# controller_rev4_2.net
KiCad netlist of a schematic drawn in EAGLE
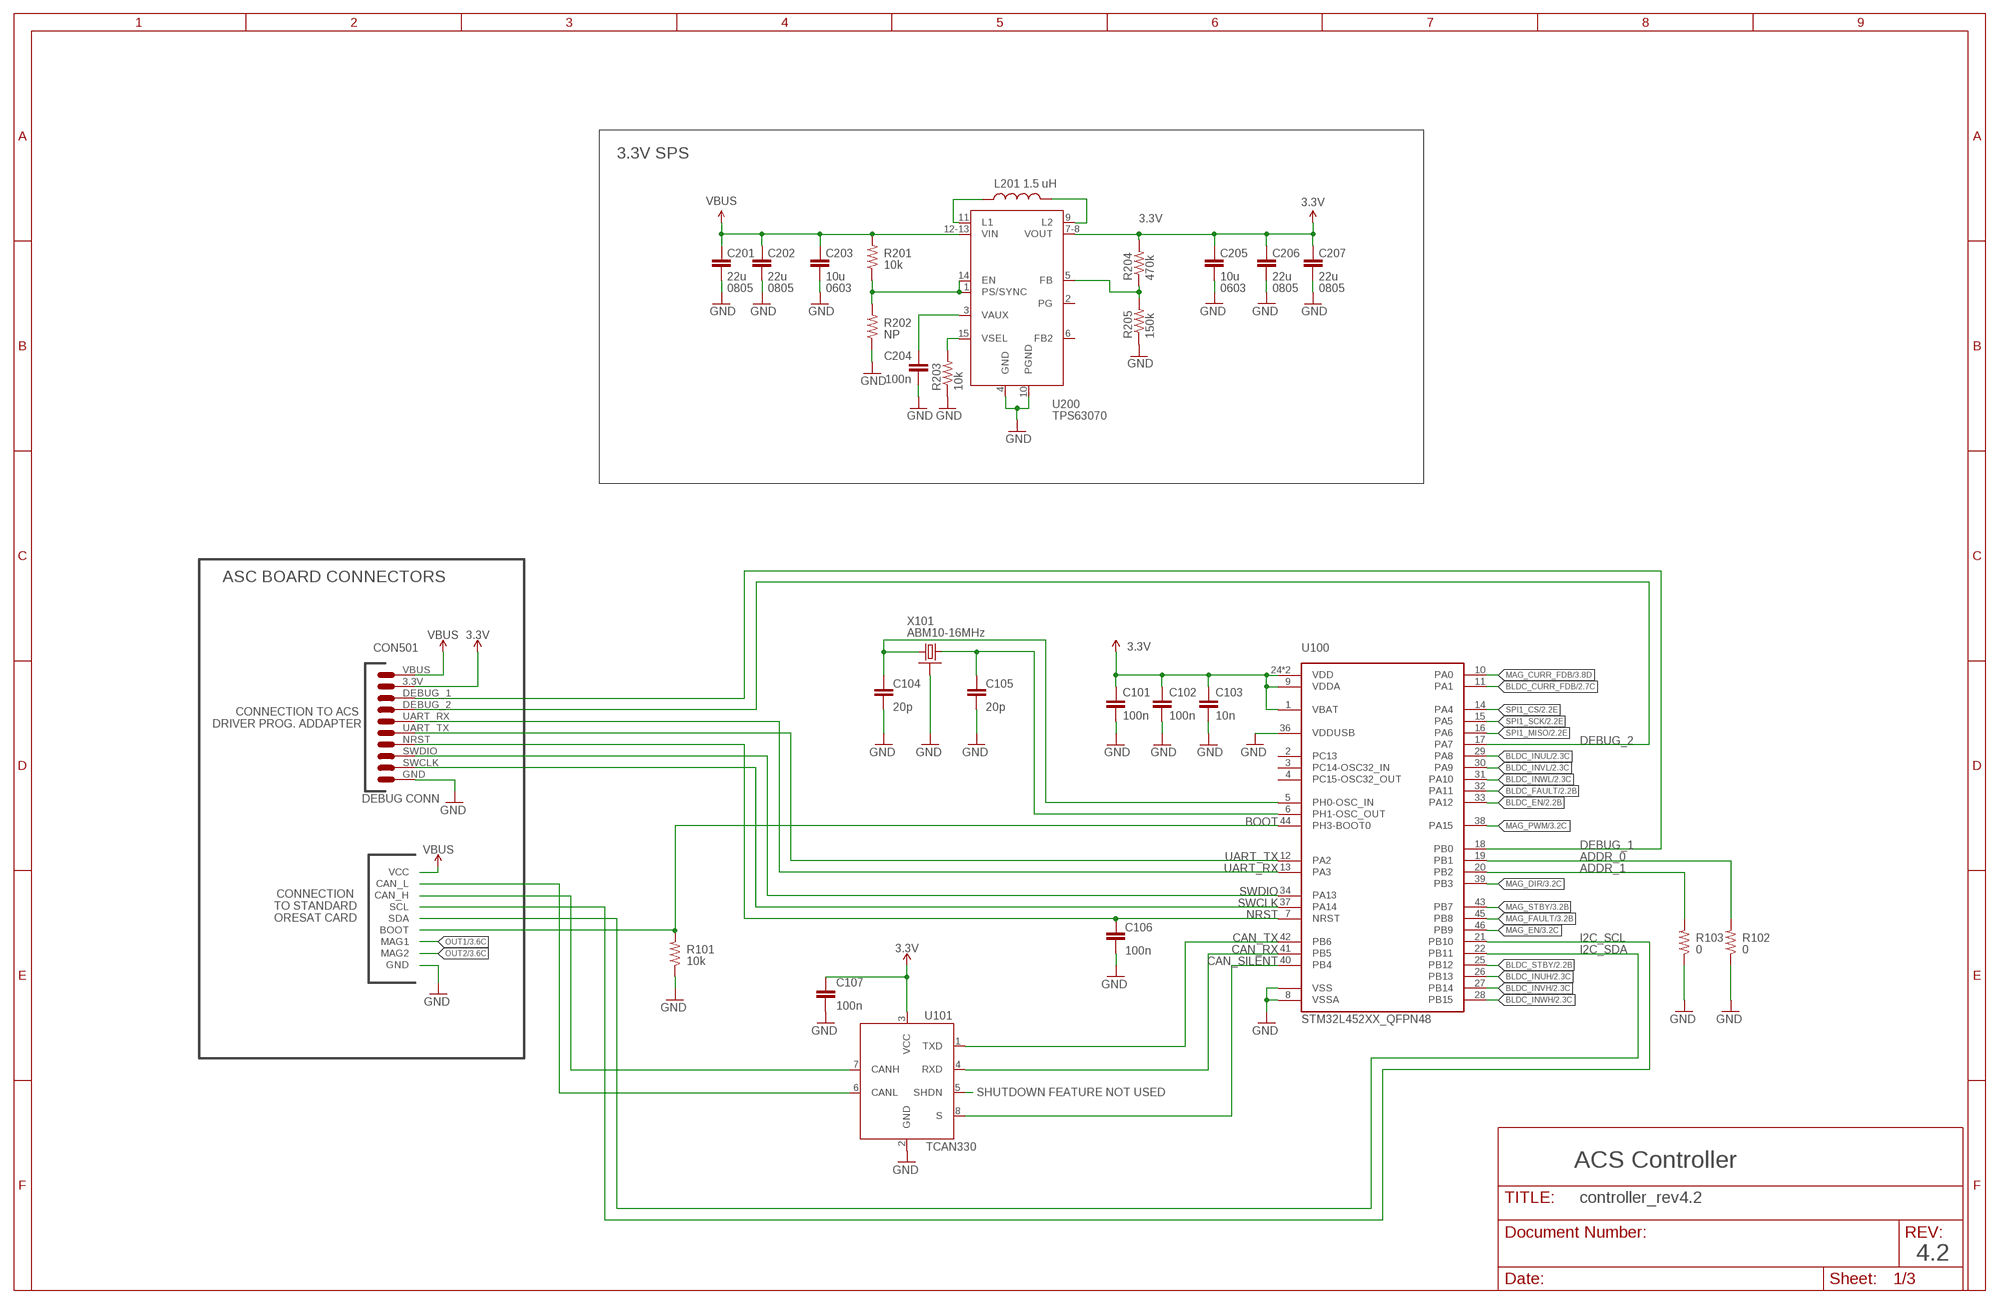
[diagram p0: schematic, sheet 1]
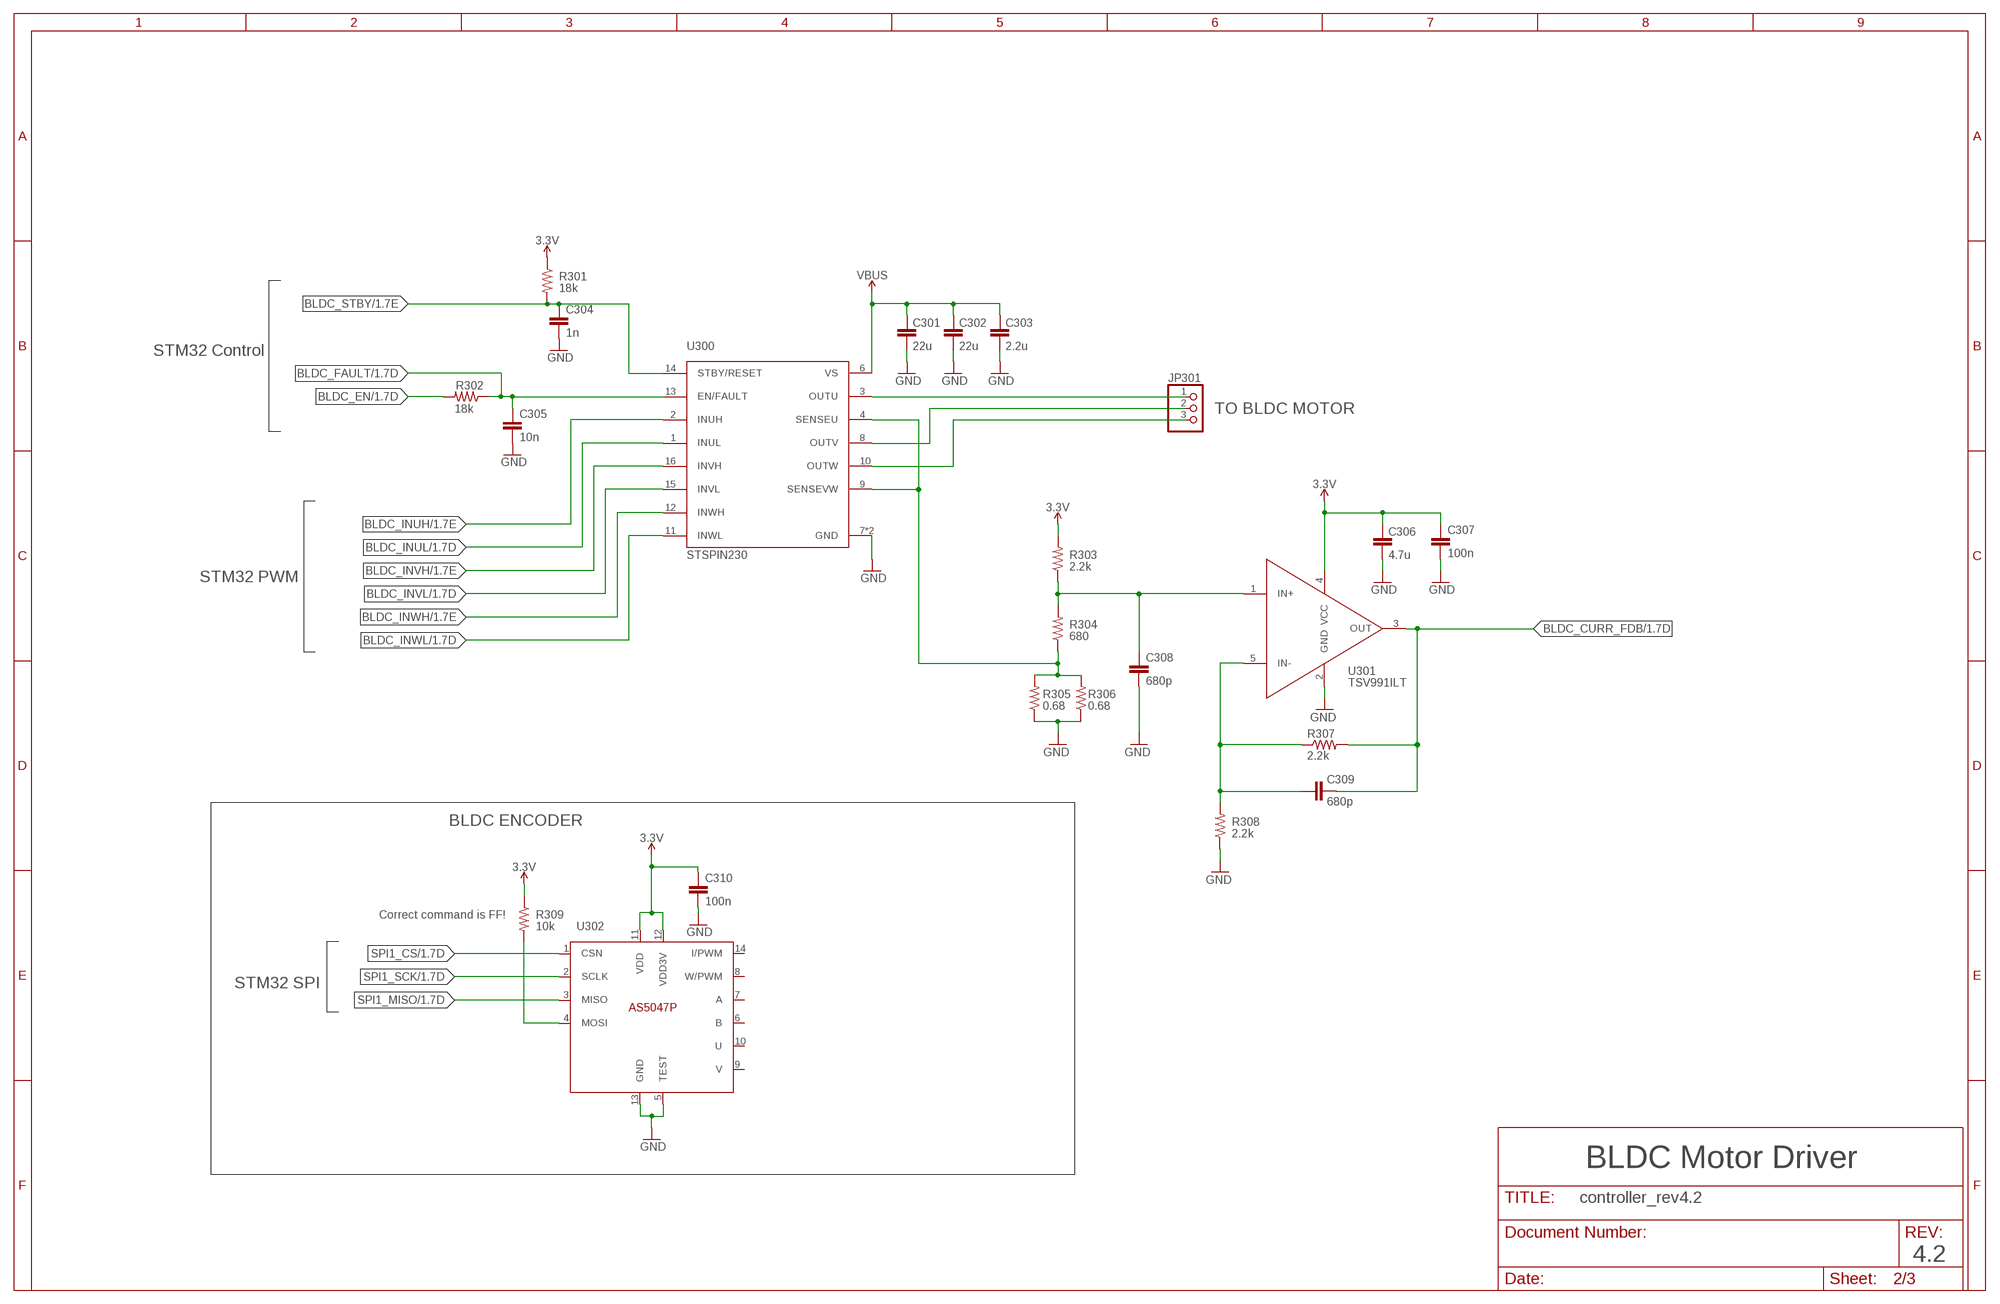
[diagram p1: schematic, sheet 2]
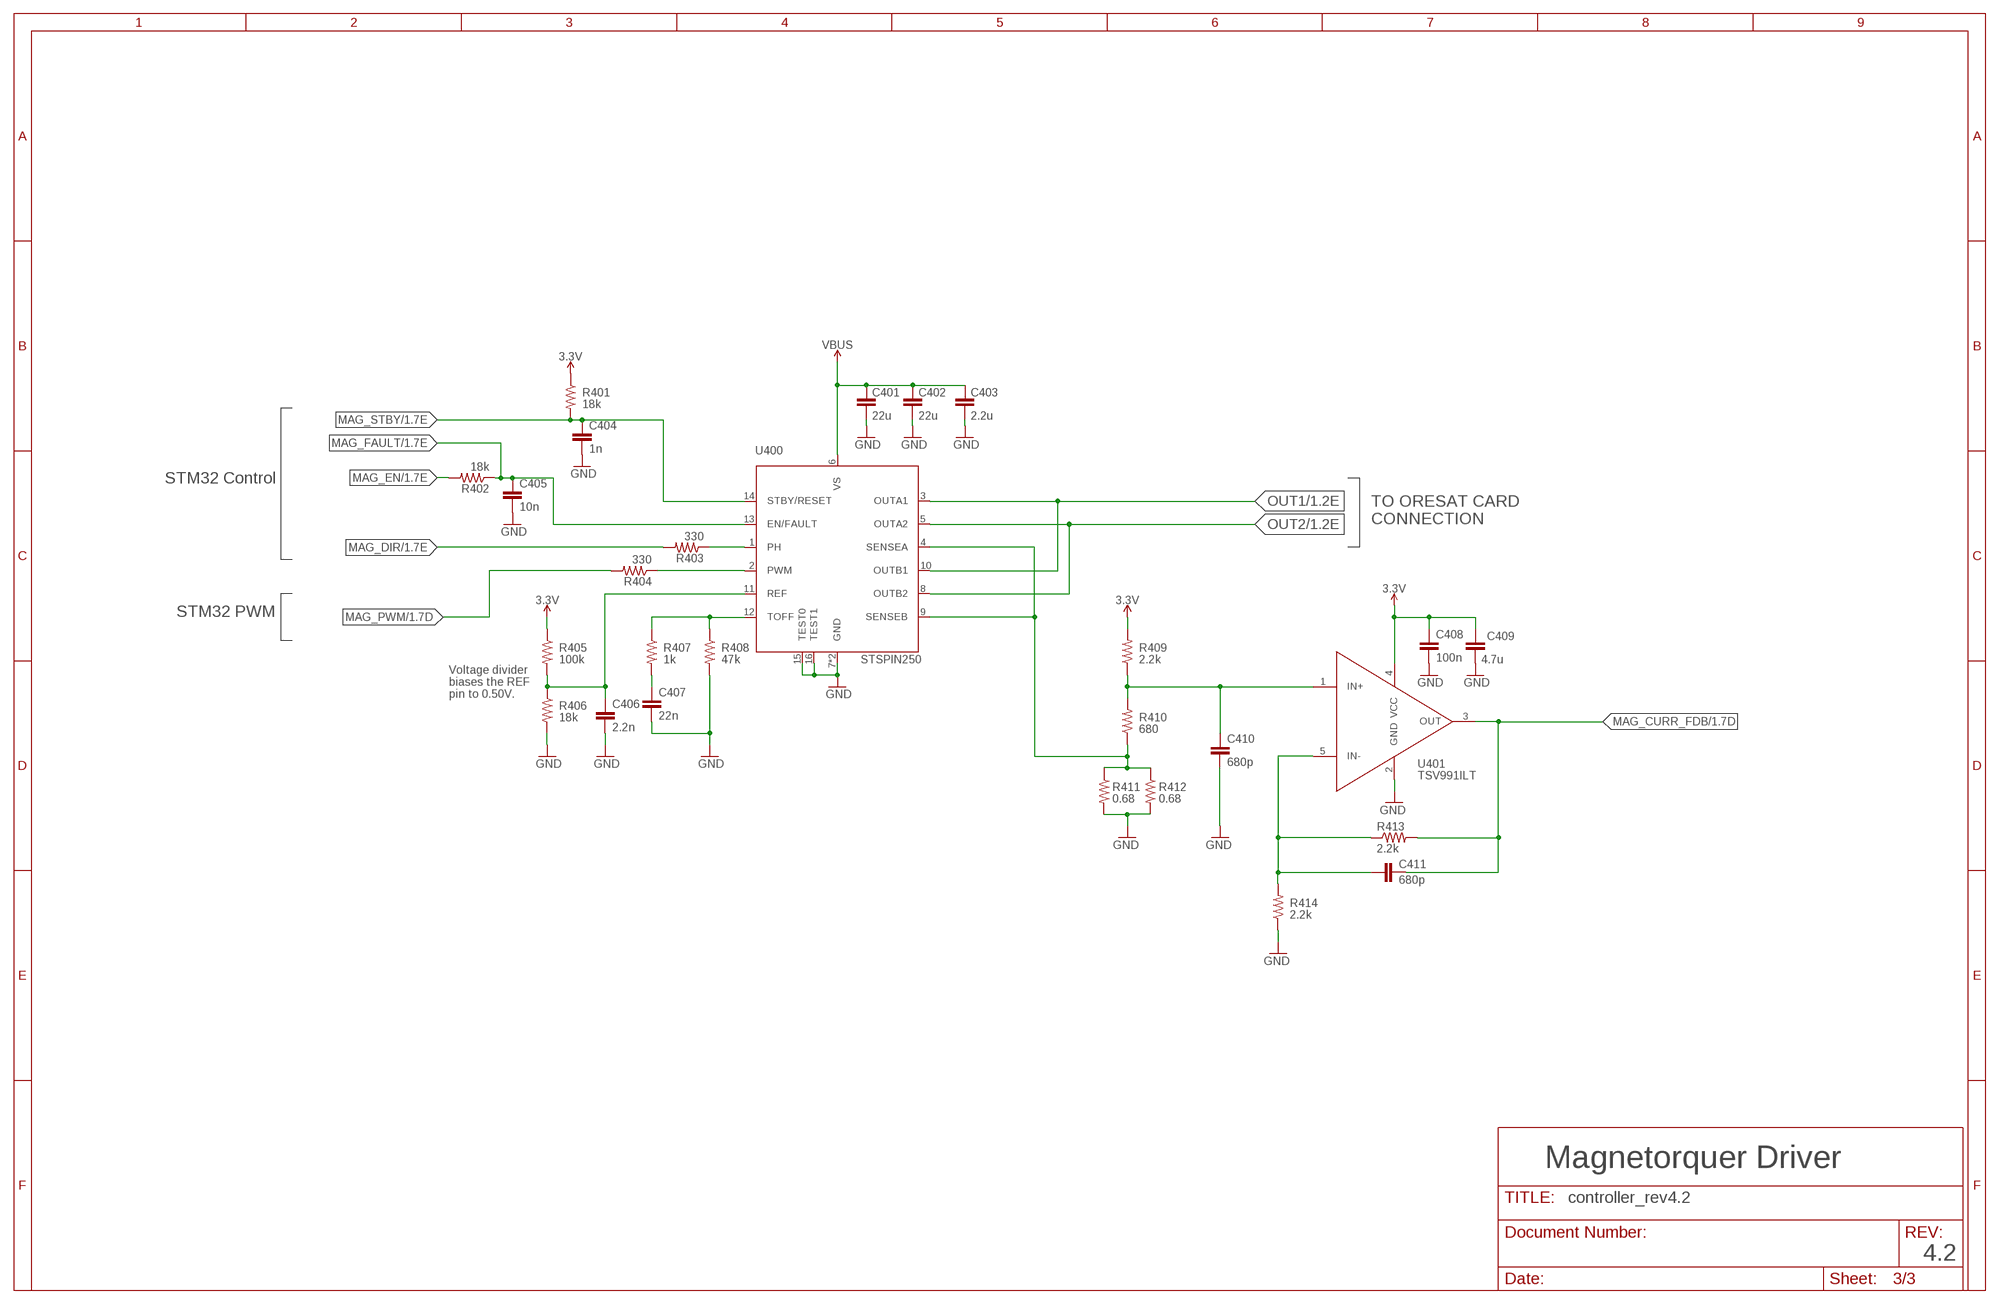
[diagram p2: schematic, sheet 3]

(export (version "E")
  (design (tool "Eeschema 10.0.6"))
  (components
    (comp (ref "C401")
      (value "22u")
      (footprint "eagle-import:.0603-B-NOSILK")
      (fields (field (name "MFR") "Samsung") (field (name "MPN") "CL05B104KO5NNNC"))
      (libsource (lib "eagle-import") (part "C-EU0603-B-NOSILK"))
    )
    (comp (ref "C402")
      (value "22u")
      (footprint "eagle-import:.0603-B-NOSILK")
      (fields (field (name "MFR") "Samsung") (field (name "MPN") "CL05B104KO5NNNC"))
      (libsource (lib "eagle-import") (part "C-EU0603-B-NOSILK"))
    )
    (comp (ref "C403")
      (value "2.2u")
      (footprint "eagle-import:.0603-B-NOSILK")
      (fields (field (name "MFR") "Samsung") (field (name "MPN") "CL05B104KO5NNNC"))
      (libsource (lib "eagle-import") (part "C-EU0603-B-NOSILK"))
    )
    (comp (ref "C404")
      (value "1n")
      (footprint "eagle-import:.0402-B-NOSILK")
      (fields (field (name "MFR") "Samsung") (field (name "MPN") "CL05B104KO5NNNC"))
      (libsource (lib "eagle-import") (part "rcl_custom_C-EU0402-B-NOSILK"))
    )
    (comp (ref "C405")
      (value "10n")
      (footprint "eagle-import:.0402-B-NOSILK")
      (fields (field (name "MFR") "Samsung") (field (name "MPN") "CL05B104KO5NNNC"))
      (libsource (lib "eagle-import") (part "rcl_custom_C-EU0402-B-NOSILK"))
    )
    (comp (ref "C406")
      (value "2.2n")
      (footprint "eagle-import:.0402-B-NOSILK")
      (fields (field (name "MFR") "Samsung") (field (name "MPN") "CL05B104KO5NNNC"))
      (libsource (lib "eagle-import") (part "rcl_custom_C-EU0402-B-NOSILK"))
    )
    (comp (ref "C407")
      (value "22n")
      (footprint "eagle-import:.0402-B-NOSILK")
      (fields (field (name "MFR") "Samsung") (field (name "MPN") "CL05B104KO5NNNC"))
      (libsource (lib "eagle-import") (part "rcl_custom_C-EU0402-B-NOSILK"))
    )
    (comp (ref "C408")
      (value "100n")
      (footprint "eagle-import:.0402-B-NOSILK")
      (fields (field (name "MFR") "Samsung") (field (name "MPN") "CL05B104KO5NNNC"))
      (libsource (lib "eagle-import") (part "rcl_custom_C-EU0402-B-NOSILK"))
    )
    (comp (ref "C409")
      (value "4.7u")
      (footprint "eagle-import:.0603-B-NOSILK")
      (fields (field (name "MFR") "Samsung") (field (name "MPN") "CL05B104KO5NNNC"))
      (libsource (lib "eagle-import") (part "C-EU0603-B-NOSILK"))
    )
    (comp (ref "C410")
      (value "680p")
      (footprint "eagle-import:.0402-B-NOSILK")
      (fields (field (name "MFR") "Samsung") (field (name "MPN") "CL05B104KO5NNNC"))
      (libsource (lib "eagle-import") (part "rcl_custom_C-EU0402-B-NOSILK"))
    )
    (comp (ref "C411")
      (value "680p")
      (footprint "eagle-import:.0402-B-NOSILK")
      (fields (field (name "MFR") "Samsung") (field (name "MPN") "CL05B104KO5NNNC"))
      (libsource (lib "eagle-import") (part "rcl_custom_C-EU0402-B-NOSILK"))
    )
    (comp (ref "R401")
      (value "18k")
      (footprint "eagle-import:.0402-B-NOSILK")
      (fields (field (name "MFR") "Samsung") (field (name "MPN") "RC1005F6653CS"))
      (libsource (lib "eagle-import") (part "rcl_custom_R-US_0402-B-NOSILK"))
    )
    (comp (ref "R402")
      (value "18k")
      (footprint "eagle-import:.0402-B-NOSILK")
      (fields (field (name "MFR") "Samsung") (field (name "MPN") "RC1005F6653CS"))
      (libsource (lib "eagle-import") (part "rcl_custom_R-US_0402-B-NOSILK"))
    )
    (comp (ref "R403")
      (value "330")
      (footprint "eagle-import:.0402-B-NOSILK")
      (fields (field (name "MFR") "Samsung") (field (name "MPN") "RC1005F6653CS"))
      (libsource (lib "eagle-import") (part "rcl_custom_R-US_0402-B-NOSILK"))
    )
    (comp (ref "R404")
      (value "330")
      (footprint "eagle-import:.0402-B-NOSILK")
      (fields (field (name "MFR") "Samsung") (field (name "MPN") "RC1005F6653CS"))
      (libsource (lib "eagle-import") (part "rcl_custom_R-US_0402-B-NOSILK"))
    )
    (comp (ref "R405")
      (value "100k")
      (footprint "eagle-import:.0402-B-NOSILK")
      (fields (field (name "MFR") "Samsung") (field (name "MPN") "RC1005F6653CS"))
      (libsource (lib "eagle-import") (part "rcl_custom_R-US_0402-B-NOSILK"))
    )
    (comp (ref "R406")
      (value "18k")
      (footprint "eagle-import:.0402-B-NOSILK")
      (fields (field (name "MFR") "Samsung") (field (name "MPN") "RC1005F6653CS"))
      (libsource (lib "eagle-import") (part "rcl_custom_R-US_0402-B-NOSILK"))
    )
    (comp (ref "R407")
      (value "1k")
      (footprint "eagle-import:.0402-B-NOSILK")
      (fields (field (name "MFR") "Samsung") (field (name "MPN") "RC1005F6653CS"))
      (libsource (lib "eagle-import") (part "rcl_custom_R-US_0402-B-NOSILK"))
    )
    (comp (ref "R408")
      (value "47k")
      (footprint "eagle-import:.0402-B-NOSILK")
      (fields (field (name "MFR") "Samsung") (field (name "MPN") "RC1005F6653CS"))
      (libsource (lib "eagle-import") (part "rcl_custom_R-US_0402-B-NOSILK"))
    )
    (comp (ref "R409")
      (value "2.2k")
      (footprint "eagle-import:.0402-B-NOSILK")
      (fields (field (name "MFR") "Samsung") (field (name "MPN") "RC1005F6653CS"))
      (libsource (lib "eagle-import") (part "rcl_custom_R-US_0402-B-NOSILK"))
    )
    (comp (ref "R410")
      (value "680")
      (footprint "eagle-import:.0402-B-NOSILK")
      (fields (field (name "MFR") "Samsung") (field (name "MPN") "RC1005F6653CS"))
      (libsource (lib "eagle-import") (part "rcl_custom_R-US_0402-B-NOSILK"))
    )
    (comp (ref "R411")
      (value "0.68")
      (footprint "eagle-import:.0805-B-NOSILK")
      (libsource (lib "eagle-import") (part "R-US_0805-B-NOSILK"))
    )
    (comp (ref "R412")
      (value "0.68")
      (footprint "eagle-import:.0805-B-NOSILK")
      (libsource (lib "eagle-import") (part "R-US_0805-B-NOSILK"))
    )
    (comp (ref "R413")
      (value "2.2k")
      (footprint "eagle-import:.0402-B-NOSILK")
      (fields (field (name "MFR") "Samsung") (field (name "MPN") "RC1005F6653CS"))
      (libsource (lib "eagle-import") (part "rcl_custom_R-US_0402-B-NOSILK"))
    )
    (comp (ref "R414")
      (value "2.2k")
      (footprint "eagle-import:.0402-B-NOSILK")
      (fields (field (name "MFR") "Samsung") (field (name "MPN") "RC1005F6653CS"))
      (libsource (lib "eagle-import") (part "rcl_custom_R-US_0402-B-NOSILK"))
    )
    (comp (ref "U400")
      (value "STSPIN250")
      (footprint "eagle-import:VFQPN")
      (libsource (lib "eagle-import") (part "STSPIN250"))
    )
    (comp (ref "U401")
      (value "TSV991ILT")
      (footprint "eagle-import:SOT23-5")
      (libsource (lib "eagle-import") (part "TSV991ILT"))
    )
    (comp (ref "C301")
      (value "22u")
      (footprint "eagle-import:.0603-B-NOSILK")
      (fields (field (name "MFR") "Samsung") (field (name "MPN") "CL05B104KO5NNNC"))
      (libsource (lib "eagle-import") (part "C-EU0603-B-NOSILK"))
    )
    (comp (ref "C302")
      (value "22u")
      (footprint "eagle-import:.0603-B-NOSILK")
      (fields (field (name "MFR") "Samsung") (field (name "MPN") "CL05B104KO5NNNC"))
      (libsource (lib "eagle-import") (part "C-EU0603-B-NOSILK"))
    )
    (comp (ref "C303")
      (value "2.2u")
      (footprint "eagle-import:.0603-B-NOSILK")
      (fields (field (name "MFR") "Samsung") (field (name "MPN") "CL05B104KO5NNNC"))
      (libsource (lib "eagle-import") (part "C-EU0603-B-NOSILK"))
    )
    (comp (ref "C304")
      (value "1n")
      (footprint "eagle-import:.0402-B-NOSILK")
      (fields (field (name "MFR") "Samsung") (field (name "MPN") "CL05B104KO5NNNC"))
      (libsource (lib "eagle-import") (part "rcl_custom_C-EU0402-B-NOSILK"))
    )
    (comp (ref "C305")
      (value "10n")
      (footprint "eagle-import:.0402-B-NOSILK")
      (fields (field (name "MFR") "Samsung") (field (name "MPN") "CL05B104KO5NNNC"))
      (libsource (lib "eagle-import") (part "rcl_custom_C-EU0402-B-NOSILK"))
    )
    (comp (ref "C306")
      (value "4.7u")
      (footprint "eagle-import:.0603-B-NOSILK")
      (fields (field (name "MFR") "Samsung") (field (name "MPN") "CL05B104KO5NNNC"))
      (libsource (lib "eagle-import") (part "C-EU0603-B-NOSILK"))
    )
    (comp (ref "C307")
      (value "100n")
      (footprint "eagle-import:.0402-B-NOSILK")
      (fields (field (name "MFR") "Samsung") (field (name "MPN") "CL05B104KO5NNNC"))
      (libsource (lib "eagle-import") (part "rcl_custom_C-EU0402-B-NOSILK"))
    )
    (comp (ref "C308")
      (value "680p")
      (footprint "eagle-import:.0402-B-NOSILK")
      (fields (field (name "MFR") "Samsung") (field (name "MPN") "CL05B104KO5NNNC"))
      (libsource (lib "eagle-import") (part "rcl_custom_C-EU0402-B-NOSILK"))
    )
    (comp (ref "C309")
      (value "680p")
      (footprint "eagle-import:.0402-B-NOSILK")
      (fields (field (name "MFR") "Samsung") (field (name "MPN") "CL05B104KO5NNNC"))
      (libsource (lib "eagle-import") (part "rcl_custom_C-EU0402-B-NOSILK"))
    )
    (comp (ref "C310")
      (value "100n")
      (footprint "eagle-import:.0402-B-NOSILK")
      (fields (field (name "MFR") "Samsung") (field (name "MPN") "CL05B104KO5NNNC"))
      (libsource (lib "eagle-import") (part "rcl_custom_C-EU0402-B-NOSILK"))
    )
    (comp (ref "JP301")
      (value "PINHD-1X03_2.00")
      (footprint "eagle-import:1X03M")
      (libsource (lib "eagle-import") (part "PINHD-1X03_2.00"))
    )
    (comp (ref "R301")
      (value "18k")
      (footprint "eagle-import:.0402-B-NOSILK")
      (fields (field (name "MFR") "Samsung") (field (name "MPN") "RC1005F6653CS"))
      (libsource (lib "eagle-import") (part "rcl_custom_R-US_0402-B-NOSILK"))
    )
    (comp (ref "R302")
      (value "18k")
      (footprint "eagle-import:.0402-B-NOSILK")
      (fields (field (name "MFR") "Samsung") (field (name "MPN") "RC1005F6653CS"))
      (libsource (lib "eagle-import") (part "rcl_custom_R-US_0402-B-NOSILK"))
    )
    (comp (ref "R303")
      (value "2.2k")
      (footprint "eagle-import:.0402-B-NOSILK")
      (fields (field (name "MFR") "Samsung") (field (name "MPN") "RC1005F6653CS"))
      (libsource (lib "eagle-import") (part "rcl_custom_R-US_0402-B-NOSILK"))
    )
    (comp (ref "R304")
      (value "680")
      (footprint "eagle-import:.0402-B-NOSILK")
      (fields (field (name "MFR") "Samsung") (field (name "MPN") "RC1005F6653CS"))
      (libsource (lib "eagle-import") (part "rcl_custom_R-US_0402-B-NOSILK"))
    )
    (comp (ref "R305")
      (value "0.68")
      (footprint "eagle-import:.0805-B-NOSILK")
      (libsource (lib "eagle-import") (part "R-US_0805-B-NOSILK"))
    )
    (comp (ref "R306")
      (value "0.68")
      (footprint "eagle-import:.0805-B-NOSILK")
      (libsource (lib "eagle-import") (part "R-US_0805-B-NOSILK"))
    )
    (comp (ref "R307")
      (value "2.2k")
      (footprint "eagle-import:.0402-B-NOSILK")
      (fields (field (name "MFR") "Samsung") (field (name "MPN") "RC1005F6653CS"))
      (libsource (lib "eagle-import") (part "rcl_custom_R-US_0402-B-NOSILK"))
    )
    (comp (ref "R308")
      (value "2.2k")
      (footprint "eagle-import:.0402-B-NOSILK")
      (fields (field (name "MFR") "Samsung") (field (name "MPN") "RC1005F6653CS"))
      (libsource (lib "eagle-import") (part "rcl_custom_R-US_0402-B-NOSILK"))
    )
    (comp (ref "R309")
      (value "10k")
      (footprint "eagle-import:.0402-B-NOSILK")
      (fields (field (name "MFR") "Samsung") (field (name "MPN") "RC1005F6653CS"))
      (libsource (lib "eagle-import") (part "rcl_custom_R-US_0402-B-NOSILK"))
    )
    (comp (ref "U300")
      (value "STSPIN230")
      (footprint "eagle-import:VFQPN")
      (libsource (lib "eagle-import") (part "STSPIN230"))
    )
    (comp (ref "U301")
      (value "TSV991ILT")
      (footprint "eagle-import:SOT23-5")
      (libsource (lib "eagle-import") (part "TSV991ILT"))
    )
    (comp (ref "U302")
      (value "AS5047P")
      (footprint "eagle-import:TSSOP14")
      (libsource (lib "eagle-import") (part "AS5047P"))
    )
    (comp (ref "C101")
      (value "100n")
      (footprint "eagle-import:.0402-B-NOSILK")
      (fields (field (name "MFR") "Samsung") (field (name "MPN") "CL05B104KO5NNNC"))
      (libsource (lib "eagle-import") (part "rcl_custom_C-EU0402-B-NOSILK"))
    )
    (comp (ref "C102")
      (value "100n")
      (footprint "eagle-import:.0402-B-NOSILK")
      (fields (field (name "MFR") "Samsung") (field (name "MPN") "CL05B104KO5NNNC"))
      (libsource (lib "eagle-import") (part "rcl_custom_C-EU0402-B-NOSILK"))
    )
    (comp (ref "C103")
      (value "10n")
      (footprint "eagle-import:.0402-B-NOSILK")
      (fields (field (name "MFR") "Samsung") (field (name "MPN") "CL05B104KO5NNNC"))
      (libsource (lib "eagle-import") (part "rcl_custom_C-EU0402-B-NOSILK"))
    )
    (comp (ref "C104")
      (value "20p")
      (footprint "eagle-import:.0402-B-NOSILK")
      (fields (field (name "MFR") "Samsung") (field (name "MPN") "CL05C200JB51PNC"))
      (libsource (lib "eagle-import") (part "rcl_custom_C-EU0402-B-NOSILK"))
    )
    (comp (ref "C105")
      (value "20p")
      (footprint "eagle-import:.0402-B-NOSILK")
      (fields (field (name "MFR") "Samsung") (field (name "MPN") "CL05C200JB51PNC"))
      (libsource (lib "eagle-import") (part "rcl_custom_C-EU0402-B-NOSILK"))
    )
    (comp (ref "C106")
      (value "100n")
      (footprint "eagle-import:.0402-B-NOSILK")
      (fields (field (name "MFR") "Samsung") (field (name "MPN") "CL05C200JB51PNC"))
      (libsource (lib "eagle-import") (part "rcl_custom_C-EU0402-B-NOSILK"))
    )
    (comp (ref "C107")
      (value "100n")
      (footprint "eagle-import:.0402-B-NOSILK")
      (fields (field (name "MFR") "Samsung") (field (name "MPN") "CL05B104KO5NNNC"))
      (libsource (lib "eagle-import") (part "rcl_custom_C-EU0402-B-NOSILK"))
    )
    (comp (ref "C201")
      (value "22u")
      (footprint "eagle-import:.0805-B-NOSILK")
      (libsource (lib "eagle-import") (part "C-EU0805-B-NOSILK"))
    )
    (comp (ref "C202")
      (value "22u")
      (footprint "eagle-import:.0805-B-NOSILK")
      (libsource (lib "eagle-import") (part "C-EU0805-B-NOSILK"))
    )
    (comp (ref "C203")
      (value "10u")
      (footprint "eagle-import:.0603-B-NOSILK")
      (fields (field (name "MFR") "Samsung") (field (name "MPN") "CL05B104KO5NNNC"))
      (libsource (lib "eagle-import") (part "C-EU0603-B-NOSILK"))
    )
    (comp (ref "C204")
      (value "100n")
      (footprint "eagle-import:.0402-B-NOSILK")
      (fields (field (name "MFR") "Samsung") (field (name "MPN") "CL05B104KO5NNNC"))
      (libsource (lib "eagle-import") (part "rcl_custom_C-EU0402-B-NOSILK"))
    )
    (comp (ref "C205")
      (value "10u")
      (footprint "eagle-import:.0603-B-NOSILK")
      (fields (field (name "MFR") "Samsung") (field (name "MPN") "CL05B104KO5NNNC"))
      (libsource (lib "eagle-import") (part "C-EU0603-B-NOSILK"))
    )
    (comp (ref "C206")
      (value "22u")
      (footprint "eagle-import:.0805-B-NOSILK")
      (libsource (lib "eagle-import") (part "C-EU0805-B-NOSILK"))
    )
    (comp (ref "C207")
      (value "22u")
      (footprint "eagle-import:.0805-B-NOSILK")
      (libsource (lib "eagle-import") (part "C-EU0805-B-NOSILK"))
    )
    (comp (ref "C501")
      (value "DEBUG_CON")
      (footprint "eagle-import:DEBUG_CON")
      (libsource (lib "eagle-import") (part "DEBUG_CON"))
    )
    (comp (ref "L201")
      (value "1.5 uH")
      (footprint "eagle-import:L-COILCRAFT-XFL4020")
      (fields (field (name "MFR") "Coilcraft") (field (name "MPN") "XFL4020-152ME"))
      (libsource (lib "eagle-import") (part "L-COILCRAFT-XFL4020"))
    )
    (comp (ref "R101")
      (value "10k")
      (footprint "eagle-import:.0402-B-NOSILK")
      (fields (field (name "MFR") "Samsung") (field (name "MPN") "RC1005F6653CS"))
      (libsource (lib "eagle-import") (part "rcl_custom_R-US_0402-B-NOSILK"))
    )
    (comp (ref "R102")
      (value "0")
      (footprint "eagle-import:.0402-B-NOSILK")
      (fields (field (name "MFR") "Samsung") (field (name "MPN") "RC1005F6653CS"))
      (libsource (lib "eagle-import") (part "rcl_custom_R-US_0402-B-NOSILK"))
    )
    (comp (ref "R103")
      (value "0")
      (footprint "eagle-import:.0402-B-NOSILK")
      (fields (field (name "MFR") "Samsung") (field (name "MPN") "RC1005F6653CS"))
      (libsource (lib "eagle-import") (part "rcl_custom_R-US_0402-B-NOSILK"))
    )
    (comp (ref "R201")
      (value "10k")
      (footprint "eagle-import:.0402-B-NOSILK")
      (fields (field (name "MFR") "Samsung") (field (name "MPN") "RC1005F6653CS"))
      (libsource (lib "eagle-import") (part "rcl_custom_R-US_0402-B-NOSILK"))
    )
    (comp (ref "R202")
      (value "NP")
      (footprint "eagle-import:.0402-B-NOSILK")
      (fields (field (name "MFR") "Samsung") (field (name "MPN") "RC1005F6653CS"))
      (libsource (lib "eagle-import") (part "rcl_custom_R-US_0402-B-NOSILK"))
    )
    (comp (ref "R203")
      (value "10k")
      (footprint "eagle-import:.0402-B-NOSILK")
      (fields (field (name "MFR") "Samsung") (field (name "MPN") "RC1005F6653CS"))
      (libsource (lib "eagle-import") (part "rcl_custom_R-US_0402-B-NOSILK"))
    )
    (comp (ref "R204")
      (value "470k")
      (footprint "eagle-import:.0402-B-NOSILK")
      (fields (field (name "MFR") "Samsung") (field (name "MPN") "RC1005F6653CS"))
      (libsource (lib "eagle-import") (part "rcl_custom_R-US_0402-B-NOSILK"))
    )
    (comp (ref "R205")
      (value "150k")
      (footprint "eagle-import:.0402-B-NOSILK")
      (fields (field (name "MFR") "Samsung") (field (name "MPN") "RC1005F6653CS"))
      (libsource (lib "eagle-import") (part "rcl_custom_R-US_0402-B-NOSILK"))
    )
    (comp (ref "U$1")
      (value "DRIVER-FLEX_CONN")
      (footprint "eagle-import:20-PAD_DRIVER-CONN")
      (libsource (lib "eagle-import") (part "DRIVER-FLEX_CONN"))
    )
    (comp (ref "U100")
      (value "STM32L452XX_QFPN48")
      (footprint "eagle-import:QFPN-48")
      (libsource (lib "eagle-import") (part "STM32L452XX_QFPN48"))
    )
    (comp (ref "U101")
      (value "TCAN330")
      (footprint "eagle-import:SOT23-8_TI-DCN")
      (fields (field (name "MFR") "Texas Instruments") (field (name "MPN") "TCAN330GDCNT"))
      (libsource (lib "eagle-import") (part "TCAN330"))
    )
    (comp (ref "U200")
      (value "TPS63070")
      (footprint "eagle-import:TPS63070X")
      (fields (field (name "MFR") "TI"))
      (libsource (lib "eagle-import") (part "TPS63070X"))
    )
    (comp (ref "X101")
      (value "ABM10-16MHz")
      (footprint "eagle-import:CRYSTAL_2.5X2")
      (fields (field (name "MFR") "ECS Inc.") (field (name "MPN") "ECS-160-10-36Q-ES-TR"))
      (libsource (lib "eagle-import") (part "CRYSTAL-WITH-GND"))
    )
  )
  (nets
    (net (code "1") (name "3.3V") (class "Default")
      (node (ref "C101") (pin "1") (pinfunction "1_1") (pintype "passive"))
      (node (ref "C102") (pin "1") (pinfunction "1_1") (pintype "passive"))
      (node (ref "C103") (pin "1") (pinfunction "1_1") (pintype "passive"))
      (node (ref "C107") (pin "1") (pinfunction "1_1") (pintype "passive"))
      (node (ref "C205") (pin "1") (pinfunction "1_1") (pintype "passive"))
      (node (ref "C206") (pin "1") (pinfunction "1_1") (pintype "passive"))
      (node (ref "C207") (pin "1") (pinfunction "1_1") (pintype "passive"))
      (node (ref "C306") (pin "1") (pinfunction "1_1") (pintype "passive"))
      (node (ref "C307") (pin "1") (pinfunction "1_1") (pintype "passive"))
      (node (ref "C310") (pin "1") (pinfunction "1_1") (pintype "passive"))
      (node (ref "C408") (pin "1") (pinfunction "1_1") (pintype "passive"))
      (node (ref "C409") (pin "1") (pinfunction "1_1") (pintype "passive"))
      (node (ref "C501") (pin "3.3V") (pinfunction "2_3.3V") (pintype "bidirectional"))
      (node (ref "R204") (pin "2") (pinfunction "2_2") (pintype "passive"))
      (node (ref "R301") (pin "1") (pinfunction "1_1") (pintype "passive"))
      (node (ref "R303") (pin "2") (pinfunction "2_2") (pintype "passive"))
      (node (ref "R309") (pin "1") (pinfunction "1_1") (pintype "passive"))
      (node (ref "R401") (pin "1") (pinfunction "1_1") (pintype "passive"))
      (node (ref "R405") (pin "1") (pinfunction "1_1") (pintype "passive"))
      (node (ref "R409") (pin "2") (pinfunction "2_2") (pintype "passive"))
      (node (ref "U100") (pin "1") (pinfunction "VBAT_1") (pintype "bidirectional"))
      (node (ref "U100") (pin "24") (pinfunction "VDD_24") (pintype "bidirectional"))
      (node (ref "U100") (pin "48") (pinfunction "VDD_48") (pintype "bidirectional"))
      (node (ref "U100") (pin "9") (pinfunction "VDDA_9") (pintype "bidirectional"))
      (node (ref "U101") (pin "3") (pinfunction "VCC_3") (pintype "power_in"))
      (node (ref "U200") (pin "7-8") (pinfunction "VOUT_7-8") (pintype "power_in"))
      (node (ref "U301") (pin "4") (pinfunction "VCC_4") (pintype "bidirectional"))
      (node (ref "U302") (pin "11") (pinfunction "VDD_11") (pintype "power_in"))
      (node (ref "U302") (pin "12") (pinfunction "VDD3V_12") (pintype "power_in"))
      (node (ref "U401") (pin "4") (pinfunction "VCC_4") (pintype "bidirectional"))
    )
    (net (code "2") (name "ADDR_0") (class "Default")
      (node (ref "R102") (pin "2") (pinfunction "2_2") (pintype "passive"))
      (node (ref "U100") (pin "19") (pinfunction "PB1_19") (pintype "bidirectional"))
    )
    (net (code "3") (name "ADDR_1") (class "Default")
      (node (ref "R103") (pin "2") (pinfunction "2_2") (pintype "passive"))
      (node (ref "U100") (pin "20") (pinfunction "PB2_20") (pintype "bidirectional"))
    )
    (net (code "4") (name "BLDC_CURR_FDB") (class "Default")
      (node (ref "C309") (pin "1") (pinfunction "1_1") (pintype "passive"))
      (node (ref "R307") (pin "2") (pinfunction "2_2") (pintype "passive"))
      (node (ref "U100") (pin "11") (pinfunction "PA1_11") (pintype "bidirectional"))
      (node (ref "U301") (pin "3") (pinfunction "OUT_3") (pintype "bidirectional"))
    )
    (net (code "5") (name "BLDC_EN") (class "Default")
      (node (ref "R302") (pin "2") (pinfunction "2_2") (pintype "passive"))
      (node (ref "U100") (pin "33") (pinfunction "PA12_33") (pintype "bidirectional"))
    )
    (net (code "6") (name "BLDC_FAULT") (class "Default")
      (node (ref "C305") (pin "1") (pinfunction "1_1") (pintype "passive"))
      (node (ref "R302") (pin "1") (pinfunction "1_1") (pintype "passive"))
      (node (ref "U100") (pin "32") (pinfunction "PA11_32") (pintype "bidirectional"))
      (node (ref "U300") (pin "13") (pinfunction "EN/FAULT_13") (pintype "bidirectional"))
    )
    (net (code "7") (name "BLDC_INUH") (class "Default")
      (node (ref "U100") (pin "26") (pinfunction "PB13_26") (pintype "bidirectional"))
      (node (ref "U300") (pin "2") (pinfunction "INUH_2") (pintype "input"))
    )
    (net (code "8") (name "BLDC_INUL") (class "Default")
      (node (ref "U100") (pin "29") (pinfunction "PA8_29") (pintype "bidirectional"))
      (node (ref "U300") (pin "1") (pinfunction "INUL_1") (pintype "input"))
    )
    (net (code "9") (name "BLDC_INVH") (class "Default")
      (node (ref "U100") (pin "27") (pinfunction "PB14_27") (pintype "bidirectional"))
      (node (ref "U300") (pin "16") (pinfunction "INVH_16") (pintype "input"))
    )
    (net (code "10") (name "BLDC_INVL") (class "Default")
      (node (ref "U100") (pin "30") (pinfunction "PA9_30") (pintype "bidirectional"))
      (node (ref "U300") (pin "15") (pinfunction "INVL_15") (pintype "input"))
    )
    (net (code "11") (name "BLDC_INWH") (class "Default")
      (node (ref "U100") (pin "28") (pinfunction "PB15_28") (pintype "bidirectional"))
      (node (ref "U300") (pin "12") (pinfunction "INWH_12") (pintype "input"))
    )
    (net (code "12") (name "BLDC_INWL") (class "Default")
      (node (ref "U100") (pin "31") (pinfunction "PA10_31") (pintype "bidirectional"))
      (node (ref "U300") (pin "11") (pinfunction "INWL_11") (pintype "input"))
    )
    (net (code "13") (name "BLDC_STBY") (class "Default")
      (node (ref "C304") (pin "1") (pinfunction "1_1") (pintype "passive"))
      (node (ref "R301") (pin "2") (pinfunction "2_2") (pintype "passive"))
      (node (ref "U100") (pin "25") (pinfunction "PB12_25") (pintype "bidirectional"))
      (node (ref "U300") (pin "14") (pinfunction "STBY/RESET_14") (pintype "input"))
    )
    (net (code "14") (name "BOOT") (class "Default")
      (node (ref "R101") (pin "2") (pinfunction "2_2") (pintype "passive"))
      (node (ref "U$1") (pin "BOOT") (pinfunction "BOOT_BOOT") (pintype "bidirectional"))
      (node (ref "U100") (pin "44") (pinfunction "PH3-BOOT0_44") (pintype "bidirectional"))
    )
    (net (code "15") (name "CAN_RX") (class "Default")
      (node (ref "U100") (pin "41") (pinfunction "PB5_41") (pintype "bidirectional"))
      (node (ref "U101") (pin "4") (pinfunction "RXD_4") (pintype "output"))
    )
    (net (code "16") (name "CAN_SILENT") (class "Default")
      (node (ref "U100") (pin "40") (pinfunction "PB4_40") (pintype "bidirectional"))
      (node (ref "U101") (pin "8") (pinfunction "S_8") (pintype "input"))
    )
    (net (code "17") (name "CAN_TX") (class "Default")
      (node (ref "U100") (pin "42") (pinfunction "PB6_42") (pintype "bidirectional"))
      (node (ref "U101") (pin "1") (pinfunction "TXD_1") (pintype "input"))
    )
    (net (code "18") (name "DEBUG_1") (class "Default")
      (node (ref "C501") (pin "DEBUG_1") (pinfunction "3_DEBUG_1") (pintype "bidirectional"))
      (node (ref "U100") (pin "18") (pinfunction "PB0_18") (pintype "bidirectional"))
    )
    (net (code "19") (name "DEBUG_2") (class "Default")
      (node (ref "C501") (pin "DEBUG_2") (pinfunction "4_DEBUG_2") (pintype "bidirectional"))
      (node (ref "U100") (pin "17") (pinfunction "PA7_17") (pintype "bidirectional"))
    )
    (net (code "20") (name "GND") (class "Default")
      (node (ref "C101") (pin "2") (pinfunction "2_2") (pintype "passive"))
      (node (ref "C102") (pin "2") (pinfunction "2_2") (pintype "passive"))
      (node (ref "C103") (pin "2") (pinfunction "2_2") (pintype "passive"))
      (node (ref "C104") (pin "2") (pinfunction "2_2") (pintype "passive"))
      (node (ref "C105") (pin "2") (pinfunction "2_2") (pintype "passive"))
      (node (ref "C106") (pin "2") (pinfunction "2_2") (pintype "passive"))
      (node (ref "C107") (pin "2") (pinfunction "2_2") (pintype "passive"))
      (node (ref "C201") (pin "2") (pinfunction "2_2") (pintype "passive"))
      (node (ref "C202") (pin "2") (pinfunction "2_2") (pintype "passive"))
      (node (ref "C203") (pin "2") (pinfunction "2_2") (pintype "passive"))
      (node (ref "C204") (pin "2") (pinfunction "2_2") (pintype "passive"))
      (node (ref "C205") (pin "2") (pinfunction "2_2") (pintype "passive"))
      (node (ref "C206") (pin "2") (pinfunction "2_2") (pintype "passive"))
      (node (ref "C207") (pin "2") (pinfunction "2_2") (pintype "passive"))
      (node (ref "C301") (pin "2") (pinfunction "2_2") (pintype "passive"))
      (node (ref "C302") (pin "2") (pinfunction "2_2") (pintype "passive"))
      (node (ref "C303") (pin "2") (pinfunction "2_2") (pintype "passive"))
      (node (ref "C304") (pin "2") (pinfunction "2_2") (pintype "passive"))
      (node (ref "C305") (pin "2") (pinfunction "2_2") (pintype "passive"))
      (node (ref "C306") (pin "2") (pinfunction "2_2") (pintype "passive"))
      (node (ref "C307") (pin "2") (pinfunction "2_2") (pintype "passive"))
      (node (ref "C308") (pin "2") (pinfunction "2_2") (pintype "passive"))
      (node (ref "C310") (pin "2") (pinfunction "2_2") (pintype "passive"))
      (node (ref "C401") (pin "2") (pinfunction "2_2") (pintype "passive"))
      (node (ref "C402") (pin "2") (pinfunction "2_2") (pintype "passive"))
      (node (ref "C403") (pin "2") (pinfunction "2_2") (pintype "passive"))
      (node (ref "C404") (pin "2") (pinfunction "2_2") (pintype "passive"))
      (node (ref "C405") (pin "2") (pinfunction "2_2") (pintype "passive"))
      (node (ref "C406") (pin "2") (pinfunction "2_2") (pintype "passive"))
      (node (ref "C407") (pin "2") (pinfunction "2_2") (pintype "passive"))
      (node (ref "C408") (pin "2") (pinfunction "2_2") (pintype "passive"))
      (node (ref "C409") (pin "2") (pinfunction "2_2") (pintype "passive"))
      (node (ref "C410") (pin "2") (pinfunction "2_2") (pintype "passive"))
      (node (ref "C501") (pin "GND") (pinfunction "10_GND") (pintype "bidirectional"))
      (node (ref "R101") (pin "1") (pinfunction "1_1") (pintype "passive"))
      (node (ref "R102") (pin "1") (pinfunction "1_1") (pintype "passive"))
      (node (ref "R103") (pin "1") (pinfunction "1_1") (pintype "passive"))
      (node (ref "R202") (pin "1") (pinfunction "1_1") (pintype "passive"))
      (node (ref "R203") (pin "1") (pinfunction "1_1") (pintype "passive"))
      (node (ref "R205") (pin "1") (pinfunction "1_1") (pintype "passive"))
      (node (ref "R305") (pin "1") (pinfunction "1_1") (pintype "passive"))
      (node (ref "R306") (pin "1") (pinfunction "1_1") (pintype "passive"))
      (node (ref "R308") (pin "1") (pinfunction "1_1") (pintype "passive"))
      (node (ref "R406") (pin "2") (pinfunction "2_2") (pintype "passive"))
      (node (ref "R408") (pin "2") (pinfunction "2_2") (pintype "passive"))
      (node (ref "R411") (pin "2") (pinfunction "2_2") (pintype "passive"))
      (node (ref "R412") (pin "2") (pinfunction "2_2") (pintype "passive"))
      (node (ref "R414") (pin "1") (pinfunction "1_1") (pintype "passive"))
      (node (ref "U$1") (pin "GND1") (pinfunction "GND_GND1") (pintype "bidirectional"))
      (node (ref "U$1") (pin "GND2") (pinfunction "GND_GND2") (pintype "bidirectional"))
      (node (ref "U$1") (pin "GND3") (pinfunction "GND_GND3") (pintype "bidirectional"))
      (node (ref "U$1") (pin "GND4") (pinfunction "GND_GND4") (pintype "bidirectional"))
      (node (ref "U$1") (pin "GND5") (pinfunction "GND_GND5") (pintype "bidirectional"))
      (node (ref "U$1") (pin "GND6") (pinfunction "GND_GND6") (pintype "bidirectional"))
      (node (ref "U$1") (pin "GND7") (pinfunction "GND_GND7") (pintype "bidirectional"))
      (node (ref "U$1") (pin "GND8") (pinfunction "GND_GND8") (pintype "bidirectional"))
      (node (ref "U$1") (pin "GND9") (pinfunction "GND_GND9") (pintype "bidirectional"))
      (node (ref "U100") (pin "23") (pinfunction "VSS_23") (pintype "bidirectional"))
      (node (ref "U100") (pin "35") (pinfunction "VSS_35") (pintype "bidirectional"))
      (node (ref "U100") (pin "36") (pinfunction "VDDUSB_36") (pintype "bidirectional"))
      (node (ref "U100") (pin "47") (pinfunction "VSS_47") (pintype "bidirectional"))
      (node (ref "U100") (pin "8") (pinfunction "VSSA_8") (pintype "bidirectional"))
      (node (ref "U100") (pin "EPAD") (pinfunction "VSS_EPAD") (pintype "bidirectional"))
      (node (ref "U101") (pin "2") (pinfunction "GND_2") (pintype "power_in"))
      (node (ref "U200") (pin "10") (pinfunction "PGND_10") (pintype "power_in"))
      (node (ref "U200") (pin "4") (pinfunction "GND_4") (pintype "power_in"))
      (node (ref "U300") (pin "7") (pinfunction "GND_7") (pintype "power_in"))
      (node (ref "U300") (pin "EPAD") (pinfunction "GND_EPAD") (pintype "power_in"))
      (node (ref "U301") (pin "2") (pinfunction "GND_2") (pintype "bidirectional"))
      (node (ref "U302") (pin "13") (pinfunction "GND_13") (pintype "power_in"))
      (node (ref "U302") (pin "5") (pinfunction "TEST_5") (pintype "power_in"))
      (node (ref "U400") (pin "15") (pinfunction "TEST0_15") (pintype "bidirectional"))
      (node (ref "U400") (pin "16") (pinfunction "TEST1_16") (pintype "bidirectional"))
      (node (ref "U400") (pin "7") (pinfunction "GND_7") (pintype "power_in"))
      (node (ref "U400") (pin "EPAD") (pinfunction "GND_EPAD") (pintype "power_in"))
      (node (ref "U401") (pin "2") (pinfunction "GND_2") (pintype "bidirectional"))
      (node (ref "X101") (pin "2") (pinfunction "SHIELD_2") (pintype "power_in"))
      (node (ref "X101") (pin "4") (pinfunction "SHIELD_4") (pintype "power_in"))
    )
    (net (code "21") (name "I2C_SCL") (class "Default")
      (node (ref "U$1") (pin "SCL") (pinfunction "SCL_SCL") (pintype "bidirectional"))
      (node (ref "U100") (pin "21") (pinfunction "PB10_21") (pintype "bidirectional"))
    )
    (net (code "22") (name "I2C_SDA") (class "Default")
      (node (ref "U$1") (pin "SDA") (pinfunction "SDA_SDA") (pintype "bidirectional"))
      (node (ref "U100") (pin "22") (pinfunction "PB11_22") (pintype "bidirectional"))
    )
    (net (code "23") (name "MAG_CURR_FDB") (class "Default")
      (node (ref "C411") (pin "1") (pinfunction "1_1") (pintype "passive"))
      (node (ref "R413") (pin "2") (pinfunction "2_2") (pintype "passive"))
      (node (ref "U100") (pin "10") (pinfunction "PA0_10") (pintype "bidirectional"))
      (node (ref "U401") (pin "3") (pinfunction "OUT_3") (pintype "bidirectional"))
    )
    (net (code "24") (name "MAG_DIR") (class "Default")
      (node (ref "R403") (pin "2") (pinfunction "2_2") (pintype "passive"))
      (node (ref "U100") (pin "39") (pinfunction "PB3_39") (pintype "bidirectional"))
    )
    (net (code "25") (name "MAG_EN") (class "Default")
      (node (ref "R402") (pin "2") (pinfunction "2_2") (pintype "passive"))
      (node (ref "U100") (pin "46") (pinfunction "PB9_46") (pintype "bidirectional"))
    )
    (net (code "26") (name "MAG_FAULT") (class "Default")
      (node (ref "C405") (pin "1") (pinfunction "1_1") (pintype "passive"))
      (node (ref "R402") (pin "1") (pinfunction "1_1") (pintype "passive"))
      (node (ref "U100") (pin "45") (pinfunction "PB8_45") (pintype "bidirectional"))
      (node (ref "U400") (pin "13") (pinfunction "EN/FAULT_13") (pintype "bidirectional"))
    )
    (net (code "27") (name "MAG_PWM") (class "Default")
      (node (ref "R404") (pin "2") (pinfunction "2_2") (pintype "passive"))
      (node (ref "U100") (pin "38") (pinfunction "PA15_38") (pintype "bidirectional"))
    )
    (net (code "28") (name "MAG_STBY") (class "Default")
      (node (ref "C404") (pin "1") (pinfunction "1_1") (pintype "passive"))
      (node (ref "R401") (pin "2") (pinfunction "2_2") (pintype "passive"))
      (node (ref "U100") (pin "43") (pinfunction "PB7_43") (pintype "bidirectional"))
      (node (ref "U400") (pin "14") (pinfunction "STBY/RESET_14") (pintype "bidirectional"))
    )
    (net (code "29") (name "NRST") (class "Default")
      (node (ref "C106") (pin "1") (pinfunction "1_1") (pintype "passive"))
      (node (ref "C501") (pin "NRST") (pinfunction "7_NRST") (pintype "bidirectional"))
      (node (ref "U100") (pin "7") (pinfunction "NRST_7") (pintype "bidirectional"))
    )
    (net (code "30") (name "Net-(C407-Pad1)") (class "Default")
      (node (ref "C407") (pin "1") (pinfunction "1_1") (pintype "passive"))
      (node (ref "R407") (pin "2") (pinfunction "2_2") (pintype "passive"))
    )
    (net (code "31") (name "Net-(U100-PH0-OSC_IN)") (class "Default")
      (node (ref "C104") (pin "1") (pinfunction "1_1") (pintype "passive"))
      (node (ref "U100") (pin "5") (pinfunction "PH0-OSC_IN_5") (pintype "bidirectional"))
      (node (ref "X101") (pin "3") (pinfunction "2_3") (pintype "passive"))
    )
    (net (code "32") (name "Net-(U100-PH1-OSC_OUT)") (class "Default")
      (node (ref "C105") (pin "1") (pinfunction "1_1") (pintype "passive"))
      (node (ref "U100") (pin "6") (pinfunction "PH1-OSC_OUT_6") (pintype "bidirectional"))
      (node (ref "X101") (pin "1") (pinfunction "1_1") (pintype "passive"))
    )
    (net (code "33") (name "Net-(U101-CANH)") (class "Default")
      (node (ref "U$1") (pin "CAN_H") (pinfunction "CAN_H_CAN_H") (pintype "bidirectional"))
      (node (ref "U101") (pin "7") (pinfunction "CANH_7") (pintype "bidirectional"))
    )
    (net (code "34") (name "Net-(U101-CANL)") (class "Default")
      (node (ref "U$1") (pin "CAN_L") (pinfunction "CAN_L_CAN_L") (pintype "bidirectional"))
      (node (ref "U101") (pin "6") (pinfunction "CANL_6") (pintype "bidirectional"))
    )
    (net (code "35") (name "Net-(U200-EN)") (class "Default")
      (node (ref "R201") (pin "1") (pinfunction "1_1") (pintype "passive"))
      (node (ref "R202") (pin "2") (pinfunction "2_2") (pintype "passive"))
      (node (ref "U200") (pin "1") (pinfunction "PS/SYNC_1") (pintype "input"))
      (node (ref "U200") (pin "14") (pinfunction "EN_14") (pintype "input"))
    )
    (net (code "36") (name "Net-(U200-FB)") (class "Default")
      (node (ref "R204") (pin "1") (pinfunction "1_1") (pintype "passive"))
      (node (ref "R205") (pin "2") (pinfunction "2_2") (pintype "passive"))
      (node (ref "U200") (pin "5") (pinfunction "FB_5") (pintype "passive"))
    )
    (net (code "37") (name "Net-(U200-L1)") (class "Default")
      (node (ref "L201") (pin "1") (pinfunction "1_1") (pintype "passive"))
      (node (ref "U200") (pin "11") (pinfunction "L1_11") (pintype "passive"))
    )
    (net (code "38") (name "Net-(U200-L2)") (class "Default")
      (node (ref "L201") (pin "2") (pinfunction "2_2") (pintype "passive"))
      (node (ref "U200") (pin "9") (pinfunction "L2_9") (pintype "passive"))
    )
    (net (code "39") (name "Net-(U200-VAUX)") (class "Default")
      (node (ref "C204") (pin "1") (pinfunction "1_1") (pintype "passive"))
      (node (ref "U200") (pin "3") (pinfunction "VAUX_3") (pintype "output"))
    )
    (net (code "40") (name "Net-(U200-VSEL)") (class "Default")
      (node (ref "R203") (pin "2") (pinfunction "2_2") (pintype "passive"))
      (node (ref "U200") (pin "15") (pinfunction "VSEL_15") (pintype "input"))
    )
    (net (code "41") (name "Net-(U300-OUTU)") (class "Default")
      (node (ref "JP301") (pin "1") (pinfunction "1_1") (pintype "passive"))
      (node (ref "U300") (pin "3") (pinfunction "OUTU_3") (pintype "output"))
    )
    (net (code "42") (name "Net-(U300-OUTV)") (class "Default")
      (node (ref "JP301") (pin "2") (pinfunction "2_2") (pintype "passive"))
      (node (ref "U300") (pin "8") (pinfunction "OUTV_8") (pintype "output"))
    )
    (net (code "43") (name "Net-(U300-OUTW)") (class "Default")
      (node (ref "JP301") (pin "3") (pinfunction "3_3") (pintype "passive"))
      (node (ref "U300") (pin "10") (pinfunction "OUTW_10") (pintype "output"))
    )
    (net (code "44") (name "Net-(U300-SENSEU)") (class "Default")
      (node (ref "R304") (pin "1") (pinfunction "1_1") (pintype "passive"))
      (node (ref "R305") (pin "2") (pinfunction "2_2") (pintype "passive"))
      (node (ref "R306") (pin "2") (pinfunction "2_2") (pintype "passive"))
      (node (ref "U300") (pin "4") (pinfunction "SENSEU_4") (pintype "output"))
      (node (ref "U300") (pin "9") (pinfunction "SENSEVW_9") (pintype "output"))
    )
    (net (code "45") (name "Net-(U301-IN+)") (class "Default")
      (node (ref "C308") (pin "1") (pinfunction "1_1") (pintype "passive"))
      (node (ref "R303") (pin "1") (pinfunction "1_1") (pintype "passive"))
      (node (ref "R304") (pin "2") (pinfunction "2_2") (pintype "passive"))
      (node (ref "U301") (pin "1") (pinfunction "IN+_1") (pintype "bidirectional"))
    )
    (net (code "46") (name "Net-(U301-IN-)") (class "Default")
      (node (ref "C309") (pin "2") (pinfunction "2_2") (pintype "passive"))
      (node (ref "R307") (pin "1") (pinfunction "1_1") (pintype "passive"))
      (node (ref "R308") (pin "2") (pinfunction "2_2") (pintype "passive"))
      (node (ref "U301") (pin "5") (pinfunction "IN-_5") (pintype "bidirectional"))
    )
    (net (code "47") (name "Net-(U302-MOSI)") (class "Default")
      (node (ref "R309") (pin "2") (pinfunction "2_2") (pintype "passive"))
      (node (ref "U302") (pin "4") (pinfunction "MOSI_4") (pintype "input"))
    )
    (net (code "48") (name "Net-(U400-PH)") (class "Default")
      (node (ref "R403") (pin "1") (pinfunction "1_1") (pintype "passive"))
      (node (ref "U400") (pin "1") (pinfunction "PH_1") (pintype "input"))
    )
    (net (code "49") (name "Net-(U400-PWM)") (class "Default")
      (node (ref "R404") (pin "1") (pinfunction "1_1") (pintype "passive"))
      (node (ref "U400") (pin "2") (pinfunction "PWM_2") (pintype "input"))
    )
    (net (code "50") (name "Net-(U400-REF)") (class "Default")
      (node (ref "C406") (pin "1") (pinfunction "1_1") (pintype "passive"))
      (node (ref "R405") (pin "2") (pinfunction "2_2") (pintype "passive"))
      (node (ref "R406") (pin "1") (pinfunction "1_1") (pintype "passive"))
      (node (ref "U400") (pin "11") (pinfunction "REF_11") (pintype "passive"))
    )
    (net (code "51") (name "Net-(U400-SENSEA)") (class "Default")
      (node (ref "R410") (pin "1") (pinfunction "1_1") (pintype "passive"))
      (node (ref "R411") (pin "1") (pinfunction "1_1") (pintype "passive"))
      (node (ref "R412") (pin "1") (pinfunction "1_1") (pintype "passive"))
      (node (ref "U400") (pin "4") (pinfunction "SENSEA_4") (pintype "output"))
      (node (ref "U400") (pin "9") (pinfunction "SENSEB_9") (pintype "output"))
    )
    (net (code "52") (name "Net-(U400-TOFF)") (class "Default")
      (node (ref "R407") (pin "1") (pinfunction "1_1") (pintype "passive"))
      (node (ref "R408") (pin "1") (pinfunction "1_1") (pintype "passive"))
      (node (ref "U400") (pin "12") (pinfunction "TOFF_12") (pintype "passive"))
    )
    (net (code "53") (name "Net-(U401-IN+)") (class "Default")
      (node (ref "C410") (pin "1") (pinfunction "1_1") (pintype "passive"))
      (node (ref "R409") (pin "1") (pinfunction "1_1") (pintype "passive"))
      (node (ref "R410") (pin "2") (pinfunction "2_2") (pintype "passive"))
      (node (ref "U401") (pin "1") (pinfunction "IN+_1") (pintype "bidirectional"))
    )
    (net (code "54") (name "Net-(U401-IN-)") (class "Default")
      (node (ref "C411") (pin "2") (pinfunction "2_2") (pintype "passive"))
      (node (ref "R413") (pin "1") (pinfunction "1_1") (pintype "passive"))
      (node (ref "R414") (pin "2") (pinfunction "2_2") (pintype "passive"))
      (node (ref "U401") (pin "5") (pinfunction "IN-_5") (pintype "bidirectional"))
    )
    (net (code "55") (name "OUT1") (class "Default")
      (node (ref "U$1") (pin "MAG1") (pinfunction "MAG1_MAG1") (pintype "bidirectional"))
      (node (ref "U400") (pin "10") (pinfunction "OUTB1_10") (pintype "output"))
      (node (ref "U400") (pin "3") (pinfunction "OUTA1_3") (pintype "output"))
    )
    (net (code "56") (name "OUT2") (class "Default")
      (node (ref "U$1") (pin "MAG2") (pinfunction "MAG2_MAG2") (pintype "bidirectional"))
      (node (ref "U400") (pin "5") (pinfunction "OUTA2_5") (pintype "output"))
      (node (ref "U400") (pin "8") (pinfunction "OUTB2_8") (pintype "output"))
    )
    (net (code "57") (name "SPI1_CS") (class "Default")
      (node (ref "U100") (pin "14") (pinfunction "PA4_14") (pintype "bidirectional"))
      (node (ref "U302") (pin "1") (pinfunction "CSN_1") (pintype "input"))
    )
    (net (code "58") (name "SPI1_MISO") (class "Default")
      (node (ref "U100") (pin "16") (pinfunction "PA6_16") (pintype "bidirectional"))
      (node (ref "U302") (pin "3") (pinfunction "MISO_3") (pintype "output"))
    )
    (net (code "59") (name "SPI1_SCK") (class "Default")
      (node (ref "U100") (pin "15") (pinfunction "PA5_15") (pintype "bidirectional"))
      (node (ref "U302") (pin "2") (pinfunction "SCLK_2") (pintype "input"))
    )
    (net (code "60") (name "SWCLK") (class "Default")
      (node (ref "C501") (pin "SWCLK") (pinfunction "9_SWCLK") (pintype "bidirectional"))
      (node (ref "U100") (pin "37") (pinfunction "PA14_37") (pintype "bidirectional"))
    )
    (net (code "61") (name "SWDIO") (class "Default")
      (node (ref "C501") (pin "SWDIO") (pinfunction "8_SWDIO") (pintype "bidirectional"))
      (node (ref "U100") (pin "34") (pinfunction "PA13_34") (pintype "bidirectional"))
    )
    (net (code "62") (name "UART_RX") (class "Default")
      (node (ref "C501") (pin "UART_RX") (pinfunction "5_UART_RX") (pintype "bidirectional"))
      (node (ref "U100") (pin "13") (pinfunction "PA3_13") (pintype "bidirectional"))
    )
    (net (code "63") (name "UART_TX") (class "Default")
      (node (ref "C501") (pin "UART_TX") (pinfunction "6_UART_TX") (pintype "bidirectional"))
      (node (ref "U100") (pin "12") (pinfunction "PA2_12") (pintype "bidirectional"))
    )
    (net (code "64") (name "VBUS") (class "Default")
      (node (ref "C201") (pin "1") (pinfunction "1_1") (pintype "passive"))
      (node (ref "C202") (pin "1") (pinfunction "1_1") (pintype "passive"))
      (node (ref "C203") (pin "1") (pinfunction "1_1") (pintype "passive"))
      (node (ref "C301") (pin "1") (pinfunction "1_1") (pintype "passive"))
      (node (ref "C302") (pin "1") (pinfunction "1_1") (pintype "passive"))
      (node (ref "C303") (pin "1") (pinfunction "1_1") (pintype "passive"))
      (node (ref "C401") (pin "1") (pinfunction "1_1") (pintype "passive"))
      (node (ref "C402") (pin "1") (pinfunction "1_1") (pintype "passive"))
      (node (ref "C403") (pin "1") (pinfunction "1_1") (pintype "passive"))
      (node (ref "C501") (pin "VBUS") (pinfunction "1_VBUS") (pintype "bidirectional"))
      (node (ref "R201") (pin "2") (pinfunction "2_2") (pintype "passive"))
      (node (ref "U$1") (pin "VCC1") (pinfunction "VCC_VCC1") (pintype "bidirectional"))
      (node (ref "U$1") (pin "VCC2") (pinfunction "VCC_VCC2") (pintype "bidirectional"))
      (node (ref "U$1") (pin "VCC3") (pinfunction "VCC_VCC3") (pintype "bidirectional"))
      (node (ref "U$1") (pin "VCC4") (pinfunction "VCC_VCC4") (pintype "bidirectional"))
      (node (ref "U200") (pin "12-13") (pinfunction "VIN_12-13") (pintype "power_in"))
      (node (ref "U300") (pin "6") (pinfunction "VS_6") (pintype "power_in"))
      (node (ref "U400") (pin "6") (pinfunction "VS_6") (pintype "power_in"))
    )
    (net (code "65") (name "unconnected-(U100-PC13-Pad2)") (class "Default")
      (node (ref "U100") (pin "2") (pinfunction "PC13_2") (pintype "bidirectional"))
    )
    (net (code "66") (name "unconnected-(U100-PC14-OSC32_IN-Pad3)") (class "Default")
      (node (ref "U100") (pin "3") (pinfunction "PC14-OSC32_IN_3") (pintype "bidirectional"))
    )
    (net (code "67") (name "unconnected-(U100-PC15-OSC32_OUT-Pad4)") (class "Default")
      (node (ref "U100") (pin "4") (pinfunction "PC15-OSC32_OUT_4") (pintype "bidirectional"))
    )
    (net (code "68") (name "unconnected-(U101-SHDN-Pad5)") (class "Default")
      (node (ref "U101") (pin "5") (pinfunction "SHDN_5") (pintype "input"))
    )
    (net (code "69") (name "unconnected-(U200-FB2-Pad6)") (class "Default")
      (node (ref "U200") (pin "6") (pinfunction "FB2_6") (pintype "passive"))
    )
    (net (code "70") (name "unconnected-(U200-PG-Pad2)") (class "Default")
      (node (ref "U200") (pin "2") (pinfunction "PG_2") (pintype "open_collector"))
    )
    (net (code "71") (name "unconnected-(U302-A-Pad7)") (class "Default")
      (node (ref "U302") (pin "7") (pinfunction "A_7") (pintype "output"))
    )
    (net (code "72") (name "unconnected-(U302-B-Pad6)") (class "Default")
      (node (ref "U302") (pin "6") (pinfunction "B_6") (pintype "output"))
    )
    (net (code "73") (name "unconnected-(U302-I{slash}PWM-Pad14)") (class "Default")
      (node (ref "U302") (pin "14") (pinfunction "I/PWM_14") (pintype "output"))
    )
    (net (code "74") (name "unconnected-(U302-U-Pad10)") (class "Default")
      (node (ref "U302") (pin "10") (pinfunction "U_10") (pintype "output"))
    )
    (net (code "75") (name "unconnected-(U302-V-Pad9)") (class "Default")
      (node (ref "U302") (pin "9") (pinfunction "V_9") (pintype "output"))
    )
    (net (code "76") (name "unconnected-(U302-W{slash}PWM-Pad8)") (class "Default")
      (node (ref "U302") (pin "8") (pinfunction "W/PWM_8") (pintype "output"))
    )
  )
)
